# Misc.net
KiCad netlist of a schematic drawn in Altium Designer
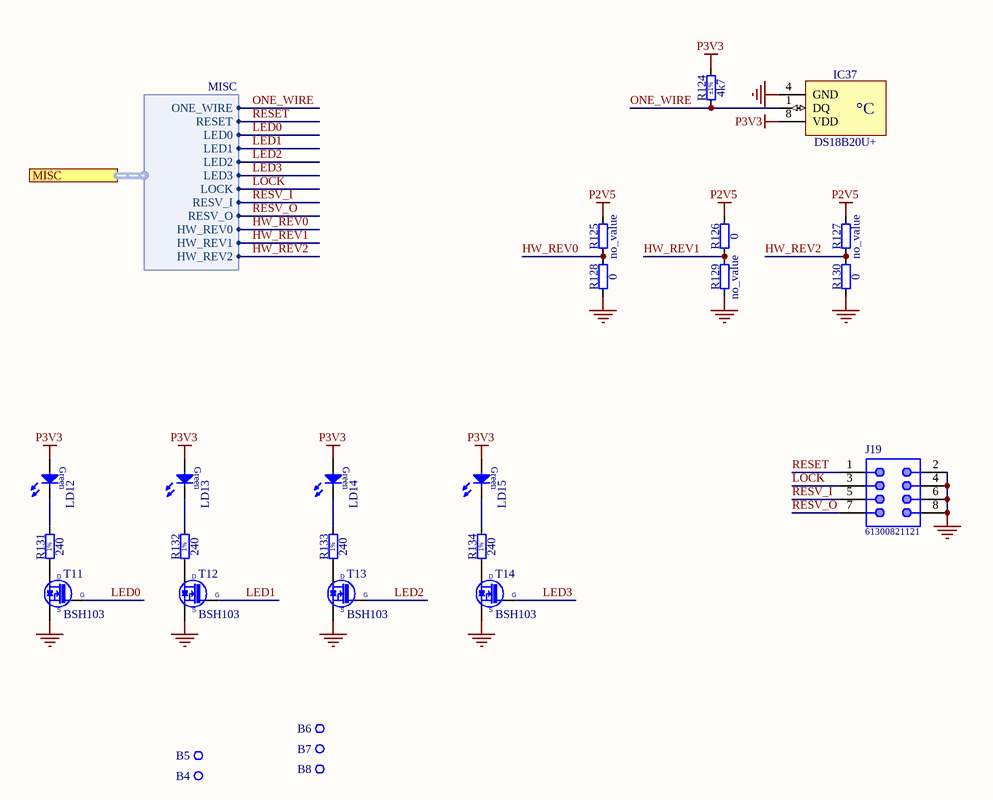
[diagram p0: Misc.SchDoc]

(export (version "E")
  (design (tool "Eeschema 10.0.6"))
  (components
    (comp (ref "B4")
      (value "Plated Hole")
      (footprint "MTG270_500")
      (description "Single Terminal Socket")
      (fields (field (name "PART NUMBER") "PLATED_HOLE2.7_PAD5.0") (field (name "AUTHOR") "CERN DEM JMW"))
      (libsource (lib "Eletro-mechanical") (part "Single Terminal Socket"))
    )
    (comp (ref "B5")
      (value "Plated Hole")
      (footprint "MTG270_500")
      (description "Single Terminal Socket")
      (fields (field (name "PART NUMBER") "PLATED_HOLE2.7_PAD5.0") (field (name "AUTHOR") "CERN DEM JMW"))
      (libsource (lib "Eletro-mechanical") (part "Single Terminal Socket"))
    )
    (comp (ref "B6")
      (value "Non Plated Hole")
      (footprint "MTG400")
      (description "Single Terminal Socket")
      (fields (field (name "PART NUMBER") "NON-PLATED_HOLE4.0") (field (name "AUTHOR") "CERN DEM JMW"))
      (libsource (lib "Eletro-mechanical") (part "Single Terminal Socket"))
    )
    (comp (ref "B7")
      (value "Non Plated Hole")
      (footprint "MTG400")
      (description "Single Terminal Socket")
      (fields (field (name "PART NUMBER") "NON-PLATED_HOLE4.0") (field (name "AUTHOR") "CERN DEM JMW"))
      (libsource (lib "Eletro-mechanical") (part "Single Terminal Socket"))
    )
    (comp (ref "B8")
      (value "Non Plated Hole")
      (footprint "MTG400")
      (description "Single Terminal Socket")
      (fields (field (name "PART NUMBER") "NON-PLATED_HOLE4.0") (field (name "AUTHOR") "CERN DEM JMW"))
      (libsource (lib "Eletro-mechanical") (part "Single Terminal Socket"))
    )
    (comp (ref "IC37")
      (value "DS18B20U+")
      (footprint "SOP65P490X110-8N")
      (description "Programmable Resolution 1-Wire Digital Thermometer")
      (fields
        (field (name "MANUFACTURER") "DALLAS MAXIM")
        (field (name "MANUFACTURER PART NUMBER") "DS18B20U")
        (field (name "AUTHOR") "CERN DEM JLC")
      )
      (libsource (lib "ICs And Semiconductors") (part "DS18B20U+"))
    )
    (comp (ref "J19")
      (value "61300821121")
      (footprint "61300821121")
      (description "WR-PHD Pin Header, THT, pitch 2.54mm, Dual Row, Vertical, 8pin")
      (fields (field (name "PUBLISHER") "Wurth Elektronik"))
      (libsource (lib "ALTIUM-WR-PHD_PIN_HEADER_SOCKET_HEADER-rev19a") (part "61300821121"))
    )
    (comp (ref "LD12")
      (value "Green")
      (footprint "LED_AVAGO_HSME-C120")
      (description "LED Green 1C 2A")
      (fields
        (field (name "PART NUMBER") "LED_AVAGO_HSME-C120")
        (field (name "MANUFACTURER") "AVAGO TECHNOLOGIES")
        (field (name "AUTHOR") "CERN DEM JMW")
      )
      (libsource (lib "ICs And Semiconductors") (part "LED Green 1C 2A"))
    )
    (comp (ref "LD13")
      (value "Green")
      (footprint "LED_AVAGO_HSME-C120")
      (description "LED Green 1C 2A")
      (fields
        (field (name "PART NUMBER") "LED_AVAGO_HSME-C120")
        (field (name "MANUFACTURER") "AVAGO TECHNOLOGIES")
        (field (name "AUTHOR") "CERN DEM JMW")
      )
      (libsource (lib "ICs And Semiconductors") (part "LED Green 1C 2A"))
    )
    (comp (ref "LD14")
      (value "Green")
      (footprint "LED_AVAGO_HSME-C120")
      (description "LED Green 1C 2A")
      (fields
        (field (name "PART NUMBER") "LED_AVAGO_HSME-C120")
        (field (name "MANUFACTURER") "AVAGO TECHNOLOGIES")
        (field (name "AUTHOR") "CERN DEM JMW")
      )
      (libsource (lib "ICs And Semiconductors") (part "LED Green 1C 2A"))
    )
    (comp (ref "LD15")
      (value "Green")
      (footprint "LED_AVAGO_HSME-C120")
      (description "LED Green 1C 2A")
      (fields
        (field (name "PART NUMBER") "LED_AVAGO_HSME-C120")
        (field (name "MANUFACTURER") "AVAGO TECHNOLOGIES")
        (field (name "AUTHOR") "CERN DEM JMW")
      )
      (libsource (lib "ICs And Semiconductors") (part "LED Green 1C 2A"))
    )
    (comp (ref "R124")
      (value "4k7")
      (footprint "RESC1005X40N")
      (description "Resistor - 1%")
      (fields
        (field (name "TOLERANCE") "±1%")
        (field (name "PART NUMBER") "R0402_4K7_1%_0.0625W_100PPM")
        (field (name "POWER") "0.0625W")
        (field (name "AUTHOR") "CERN DEM JLC")
      )
      (libsource (lib "Resistors") (part "Resistor - 1%"))
    )
    (comp (ref "R125")
      (value "no_value")
      (footprint "RESC1005X40N")
      (description "Resistor")
      (fields
        (field (name "PART NUMBER") "R0402_0R_JUMPER")
        (field (name "MANUFACTURER") "GENERIC")
        (field (name "AUTHOR") "CERN DEM JLC")
      )
      (libsource (lib "Resistors") (part "Resistor"))
    )
    (comp (ref "R126")
      (value "0")
      (footprint "RESC1005X40N")
      (description "Resistor")
      (fields
        (field (name "PART NUMBER") "R0402_0R_JUMPER")
        (field (name "MANUFACTURER") "GENERIC")
        (field (name "AUTHOR") "CERN DEM JLC")
      )
      (libsource (lib "Resistors") (part "Resistor"))
    )
    (comp (ref "R127")
      (value "no_value")
      (footprint "RESC1005X40N")
      (description "Resistor")
      (fields
        (field (name "PART NUMBER") "R0402_0R_JUMPER")
        (field (name "MANUFACTURER") "GENERIC")
        (field (name "AUTHOR") "CERN DEM JLC")
      )
      (libsource (lib "Resistors") (part "Resistor"))
    )
    (comp (ref "R128")
      (value "0")
      (footprint "RESC1005X40N")
      (description "Resistor")
      (fields
        (field (name "PART NUMBER") "R0402_0R_JUMPER")
        (field (name "MANUFACTURER") "GENERIC")
        (field (name "AUTHOR") "CERN DEM JLC")
      )
      (libsource (lib "Resistors") (part "Resistor"))
    )
    (comp (ref "R129")
      (value "no_value")
      (footprint "RESC1005X40N")
      (description "Resistor")
      (fields
        (field (name "PART NUMBER") "R0402_0R_JUMPER")
        (field (name "MANUFACTURER") "GENERIC")
        (field (name "AUTHOR") "CERN DEM JLC")
      )
      (libsource (lib "Resistors") (part "Resistor"))
    )
    (comp (ref "R130")
      (value "0")
      (footprint "RESC1005X40N")
      (description "Resistor")
      (fields
        (field (name "PART NUMBER") "R0402_0R_JUMPER")
        (field (name "MANUFACTURER") "GENERIC")
        (field (name "AUTHOR") "CERN DEM JLC")
      )
      (libsource (lib "Resistors") (part "Resistor"))
    )
    (comp (ref "R131")
      (value "240")
      (footprint "RESC1005X40N")
      (description "Resistor - 1%")
      (fields
        (field (name "PART NUMBER") "R0402_240R_1%_0.0625W_100PPM")
        (field (name "POWER") "0.0625W")
        (field (name "AUTHOR") "CERN DEM JLC")
      )
      (libsource (lib "Resistors") (part "Resistor - 1%"))
    )
    (comp (ref "R132")
      (value "240")
      (footprint "RESC1005X40N")
      (description "Resistor - 1%")
      (fields
        (field (name "PART NUMBER") "R0402_240R_1%_0.0625W_100PPM")
        (field (name "POWER") "0.0625W")
        (field (name "AUTHOR") "CERN DEM JLC")
      )
      (libsource (lib "Resistors") (part "Resistor - 1%"))
    )
    (comp (ref "R133")
      (value "240")
      (footprint "RESC1005X40N")
      (description "Resistor - 1%")
      (fields
        (field (name "PART NUMBER") "R0402_240R_1%_0.0625W_100PPM")
        (field (name "POWER") "0.0625W")
        (field (name "AUTHOR") "CERN DEM JLC")
      )
      (libsource (lib "Resistors") (part "Resistor - 1%"))
    )
    (comp (ref "R134")
      (value "240")
      (footprint "RESC1005X40N")
      (description "Resistor - 1%")
      (fields
        (field (name "PART NUMBER") "R0402_240R_1%_0.0625W_100PPM")
        (field (name "POWER") "0.0625W")
        (field (name "AUTHOR") "CERN DEM JLC")
      )
      (libsource (lib "Resistors") (part "Resistor - 1%"))
    )
    (comp (ref "T11")
      (value "BSH103")
      (footprint "SOT95P230X110-3N")
      (description "N-CHANNEL MOSFET WITH DIODE")
      (fields (field (name "MANUFACTURER") "NEXPERIA") (field (name "AUTHOR") "CERN DEM JLC"))
      (libsource (lib "ICs And Semiconductors") (part "N-MOSFET-D 1G 2S 3D"))
    )
    (comp (ref "T12")
      (value "BSH103")
      (footprint "SOT95P230X110-3N")
      (description "N-CHANNEL MOSFET WITH DIODE")
      (fields (field (name "MANUFACTURER") "NEXPERIA") (field (name "AUTHOR") "CERN DEM JLC"))
      (libsource (lib "ICs And Semiconductors") (part "N-MOSFET-D 1G 2S 3D"))
    )
    (comp (ref "T13")
      (value "BSH103")
      (footprint "SOT95P230X110-3N")
      (description "N-CHANNEL MOSFET WITH DIODE")
      (fields (field (name "MANUFACTURER") "NEXPERIA") (field (name "AUTHOR") "CERN DEM JLC"))
      (libsource (lib "ICs And Semiconductors") (part "N-MOSFET-D 1G 2S 3D"))
    )
    (comp (ref "T14")
      (value "BSH103")
      (footprint "SOT95P230X110-3N")
      (description "N-CHANNEL MOSFET WITH DIODE")
      (fields (field (name "MANUFACTURER") "NEXPERIA") (field (name "AUTHOR") "CERN DEM JLC"))
      (libsource (lib "ICs And Semiconductors") (part "N-MOSFET-D 1G 2S 3D"))
    )
  )
  (nets
    (net (code "2") (name "/HW_REV0") (class "Default")
      (node (ref "R125") (pin "1") (pinfunction "1_1") (pintype "passive"))
      (node (ref "R128") (pin "2") (pinfunction "2_2") (pintype "passive"))
    )
    (net (code "3") (name "/HW_REV1") (class "Default")
      (node (ref "R126") (pin "1") (pinfunction "1_1") (pintype "passive"))
      (node (ref "R129") (pin "2") (pinfunction "2_2") (pintype "passive"))
    )
    (net (code "4") (name "/HW_REV2") (class "Default")
      (node (ref "R127") (pin "1") (pinfunction "1_1") (pintype "passive"))
      (node (ref "R130") (pin "2") (pinfunction "2_2") (pintype "passive"))
    )
    (net (code "5") (name "/LED0") (class "Default")
      (node (ref "T11") (pin "1") (pinfunction "G_1") (pintype "passive"))
    )
    (net (code "6") (name "/LED1") (class "Default")
      (node (ref "T12") (pin "1") (pinfunction "G_1") (pintype "passive"))
    )
    (net (code "7") (name "/LED2") (class "Default")
      (node (ref "T13") (pin "1") (pinfunction "G_1") (pintype "passive"))
    )
    (net (code "8") (name "/LED3") (class "Default")
      (node (ref "T14") (pin "1") (pinfunction "G_1") (pintype "passive"))
    )
    (net (code "9") (name "/LOCK") (class "Default")
      (node (ref "J19") (pin "3") (pinfunction "3_3") (pintype "passive"))
    )
    (net (code "10") (name "/ONE_WIRE") (class "Default")
      (node (ref "IC37") (pin "1") (pinfunction "DQ_1") (pintype "bidirectional"))
      (node (ref "R124") (pin "1") (pinfunction "1_1") (pintype "passive"))
    )
    (net (code "11") (name "/RESET") (class "Default")
      (node (ref "J19") (pin "1") (pinfunction "1_1") (pintype "passive"))
    )
    (net (code "12") (name "/RESV_I") (class "Default")
      (node (ref "J19") (pin "5") (pinfunction "5_5") (pintype "passive"))
    )
    (net (code "13") (name "/RESV_O") (class "Default")
      (node (ref "J19") (pin "7") (pinfunction "7_7") (pintype "passive"))
    )
    (net (code "15") (name "GND") (class "Default")
      (node (ref "IC37") (pin "4") (pinfunction "GND_4") (pintype "power_in"))
      (node (ref "J19") (pin "2") (pinfunction "2_2") (pintype "passive"))
      (node (ref "J19") (pin "4") (pinfunction "4_4") (pintype "passive"))
      (node (ref "J19") (pin "6") (pinfunction "6_6") (pintype "passive"))
      (node (ref "J19") (pin "8") (pinfunction "8_8") (pintype "passive"))
      (node (ref "R128") (pin "1") (pinfunction "1_1") (pintype "passive"))
      (node (ref "R129") (pin "1") (pinfunction "1_1") (pintype "passive"))
      (node (ref "R130") (pin "1") (pinfunction "1_1") (pintype "passive"))
      (node (ref "T11") (pin "2") (pinfunction "S_2") (pintype "passive"))
      (node (ref "T12") (pin "2") (pinfunction "S_2") (pintype "passive"))
      (node (ref "T13") (pin "2") (pinfunction "S_2") (pintype "passive"))
      (node (ref "T14") (pin "2") (pinfunction "S_2") (pintype "passive"))
    )
    (net (code "16") (name "Net-(LD12-C)") (class "Default")
      (node (ref "LD12") (pin "1") (pinfunction "C_1") (pintype "passive"))
      (node (ref "R131") (pin "2") (pinfunction "2_2") (pintype "passive"))
    )
    (net (code "17") (name "Net-(LD13-C)") (class "Default")
      (node (ref "LD13") (pin "1") (pinfunction "C_1") (pintype "passive"))
      (node (ref "R132") (pin "2") (pinfunction "2_2") (pintype "passive"))
    )
    (net (code "18") (name "Net-(LD14-C)") (class "Default")
      (node (ref "LD14") (pin "1") (pinfunction "C_1") (pintype "passive"))
      (node (ref "R133") (pin "2") (pinfunction "2_2") (pintype "passive"))
    )
    (net (code "19") (name "Net-(LD15-C)") (class "Default")
      (node (ref "LD15") (pin "1") (pinfunction "C_1") (pintype "passive"))
      (node (ref "R134") (pin "2") (pinfunction "2_2") (pintype "passive"))
    )
    (net (code "20") (name "Net-(T11-D)") (class "Default")
      (node (ref "R131") (pin "1") (pinfunction "1_1") (pintype "passive"))
      (node (ref "T11") (pin "3") (pinfunction "D_3") (pintype "passive"))
    )
    (net (code "21") (name "Net-(T12-D)") (class "Default")
      (node (ref "R132") (pin "1") (pinfunction "1_1") (pintype "passive"))
      (node (ref "T12") (pin "3") (pinfunction "D_3") (pintype "passive"))
    )
    (net (code "22") (name "Net-(T13-D)") (class "Default")
      (node (ref "R133") (pin "1") (pinfunction "1_1") (pintype "passive"))
      (node (ref "T13") (pin "3") (pinfunction "D_3") (pintype "passive"))
    )
    (net (code "23") (name "Net-(T14-D)") (class "Default")
      (node (ref "R134") (pin "1") (pinfunction "1_1") (pintype "passive"))
      (node (ref "T14") (pin "3") (pinfunction "D_3") (pintype "passive"))
    )
    (net (code "24") (name "P2V5") (class "Default")
      (node (ref "R125") (pin "2") (pinfunction "2_2") (pintype "passive"))
      (node (ref "R126") (pin "2") (pinfunction "2_2") (pintype "passive"))
      (node (ref "R127") (pin "2") (pinfunction "2_2") (pintype "passive"))
    )
    (net (code "25") (name "P3V3") (class "Default")
      (node (ref "IC37") (pin "8") (pinfunction "VDD_8") (pintype "power_in"))
      (node (ref "LD12") (pin "2") (pinfunction "A_2") (pintype "passive"))
      (node (ref "LD13") (pin "2") (pinfunction "A_2") (pintype "passive"))
      (node (ref "LD14") (pin "2") (pinfunction "A_2") (pintype "passive"))
      (node (ref "LD15") (pin "2") (pinfunction "A_2") (pintype "passive"))
      (node (ref "R124") (pin "2") (pinfunction "2_2") (pintype "passive"))
    )
    (net (code "26") (name "unconnected-(B4-Pad1)") (class "Default")
      (node (ref "B4") (pin "1") (pinfunction "1_1") (pintype "bidirectional"))
    )
    (net (code "27") (name "unconnected-(B5-Pad1)") (class "Default")
      (node (ref "B5") (pin "1") (pinfunction "1_1") (pintype "bidirectional"))
    )
    (net (code "28") (name "unconnected-(B6-Pad1)") (class "Default")
      (node (ref "B6") (pin "1") (pinfunction "1_1") (pintype "bidirectional"))
    )
    (net (code "29") (name "unconnected-(B7-Pad1)") (class "Default")
      (node (ref "B7") (pin "1") (pinfunction "1_1") (pintype "bidirectional"))
    )
    (net (code "30") (name "unconnected-(B8-Pad1)") (class "Default")
      (node (ref "B8") (pin "1") (pinfunction "1_1") (pintype "bidirectional"))
    )
  )
)
